# chessclock.net
KiCad netlist of a schematic drawn in EAGLE
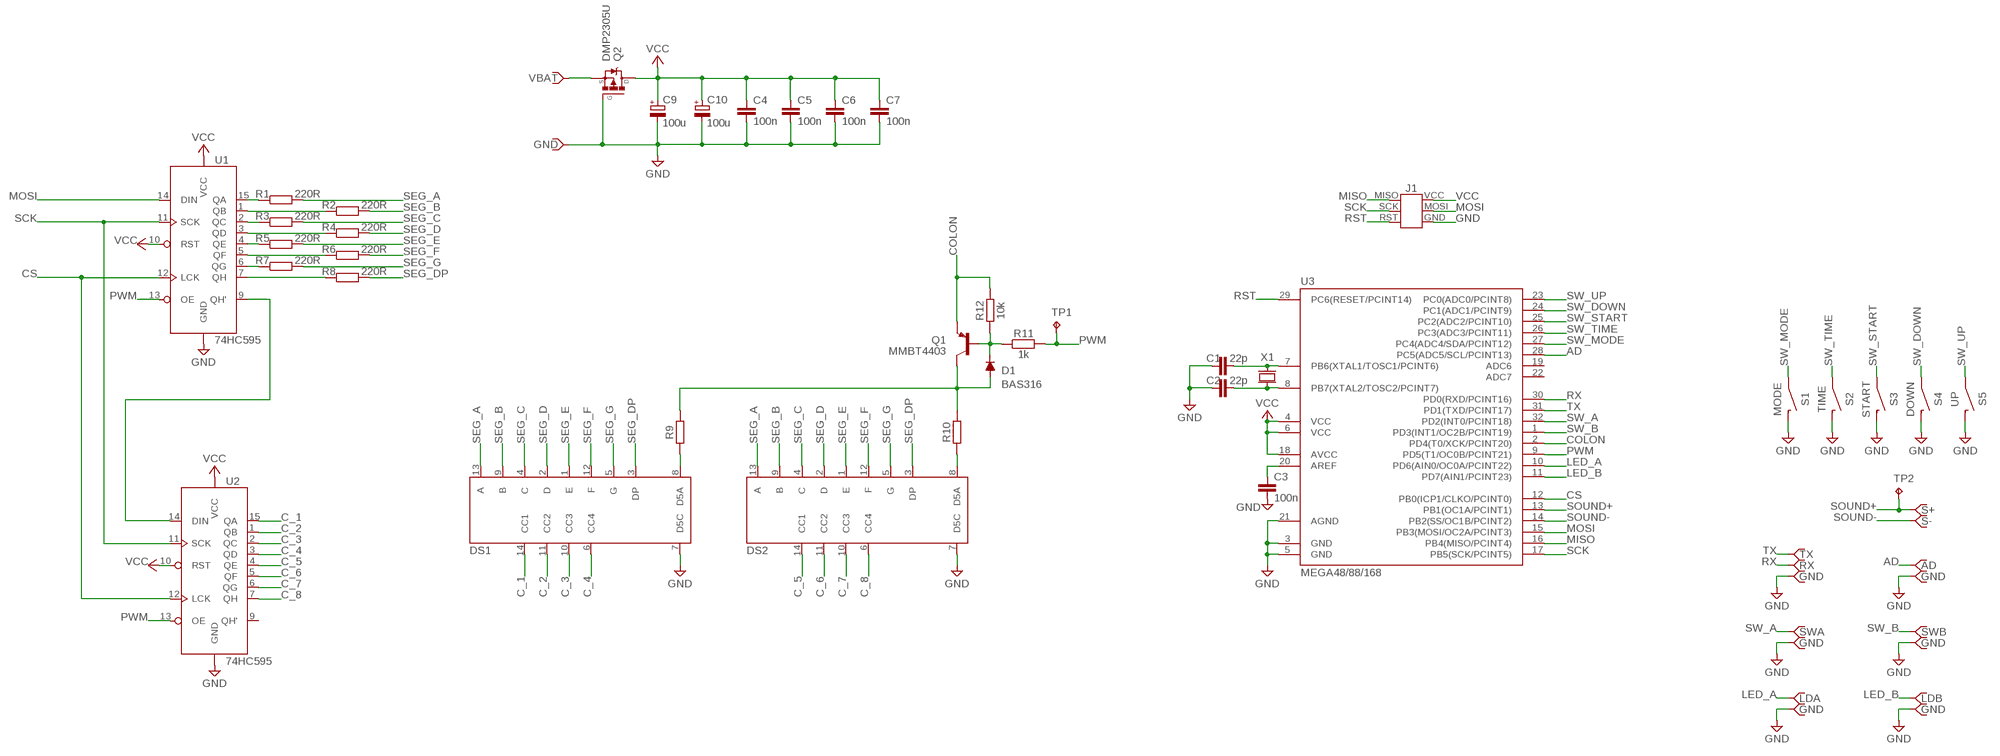
[diagram p0: schematic, sheet 1]

(export (version "E")
  (design (tool "Eeschema 10.0.6"))
  (components
    (comp (ref "C1")
      (value "22p")
      (footprint "eagle-import:C_0603")
      (libsource (lib "eagle-import") (part "CAPACITOR0603"))
    )
    (comp (ref "C2")
      (value "22p")
      (footprint "eagle-import:C_0603")
      (libsource (lib "eagle-import") (part "CAPACITOR0603"))
    )
    (comp (ref "C3")
      (value "100n")
      (footprint "eagle-import:C_0603")
      (libsource (lib "eagle-import") (part "CAPACITOR0603"))
    )
    (comp (ref "C4")
      (value "100n")
      (footprint "eagle-import:C_0603")
      (libsource (lib "eagle-import") (part "CAPACITOR0603"))
    )
    (comp (ref "C5")
      (value "100n")
      (footprint "eagle-import:C_0603")
      (libsource (lib "eagle-import") (part "CAPACITOR0603"))
    )
    (comp (ref "C6")
      (value "100n")
      (footprint "eagle-import:C_0603")
      (libsource (lib "eagle-import") (part "CAPACITOR0603"))
    )
    (comp (ref "C7")
      (value "100n")
      (footprint "eagle-import:C_0603")
      (libsource (lib "eagle-import") (part "CAPACITOR0603"))
    )
    (comp (ref "C9")
      (value "100u")
      (footprint "eagle-import:C_E_TH_FLAT_L_5MM")
      (libsource (lib "eagle-import") (part "CAPACITOR_POLARISEDTH_FLAT_L_5MM"))
    )
    (comp (ref "C10")
      (value "100u")
      (footprint "eagle-import:C_E_TH_FLAT_L_5MM")
      (libsource (lib "eagle-import") (part "CAPACITOR_POLARISEDTH_FLAT_L_5MM"))
    )
    (comp (ref "D1")
      (value "BAS316")
      (footprint "eagle-import:SOD323")
      (libsource (lib "eagle-import") (part "BAS316"))
    )
    (comp (ref "DS1")
      (value "SLR0564FR1C4BD-3.5")
      (footprint "eagle-import:SLR0564FR1C4BD-3.5")
      (libsource (lib "eagle-import") (part "SLR0564FR1C4BD-3.5"))
    )
    (comp (ref "DS2")
      (value "SLR0564FR1C4BD-3.5")
      (footprint "eagle-import:SLR0564FR1C4BD-3.5")
      (libsource (lib "eagle-import") (part "SLR0564FR1C4BD-3.5"))
    )
    (comp (ref "J1")
      (value "AVRISPVERT")
      (footprint "eagle-import:AVRISP")
      (libsource (lib "eagle-import") (part "AVRISPVERT"))
    )
    (comp (ref "P1")
      (value "SWA")
      (footprint "eagle-import:CON_PIN_2MM")
      (libsource (lib "eagle-import") (part "CON_PIN_2MM"))
    )
    (comp (ref "P2")
      (value "GND")
      (footprint "eagle-import:CON_PIN_2MM")
      (libsource (lib "eagle-import") (part "CON_PIN_2MM"))
    )
    (comp (ref "P3")
      (value "LDA")
      (footprint "eagle-import:CON_PIN_2MM")
      (libsource (lib "eagle-import") (part "CON_PIN_2MM"))
    )
    (comp (ref "P4")
      (value "GND")
      (footprint "eagle-import:CON_PIN_2MM")
      (libsource (lib "eagle-import") (part "CON_PIN_2MM"))
    )
    (comp (ref "P5")
      (value "SWB")
      (footprint "eagle-import:CON_PIN_2MM")
      (libsource (lib "eagle-import") (part "CON_PIN_2MM"))
    )
    (comp (ref "P6")
      (value "GND")
      (footprint "eagle-import:CON_PIN_2MM")
      (libsource (lib "eagle-import") (part "CON_PIN_2MM"))
    )
    (comp (ref "P7")
      (value "LDB")
      (footprint "eagle-import:CON_PIN_2MM")
      (libsource (lib "eagle-import") (part "CON_PIN_2MM"))
    )
    (comp (ref "P8")
      (value "GND")
      (footprint "eagle-import:CON_PIN_2MM")
      (libsource (lib "eagle-import") (part "CON_PIN_2MM"))
    )
    (comp (ref "P9")
      (value "GND")
      (footprint "eagle-import:CON_PIN_2MM")
      (libsource (lib "eagle-import") (part "CON_PIN_2MM"))
    )
    (comp (ref "P10")
      (value "VBAT")
      (footprint "eagle-import:CON_PIN_2MM")
      (libsource (lib "eagle-import") (part "CON_PIN_2MM"))
    )
    (comp (ref "P11")
      (value "S+")
      (footprint "eagle-import:CON_PIN_2MM")
      (libsource (lib "eagle-import") (part "CON_PIN_2MM"))
    )
    (comp (ref "P12")
      (value "S-")
      (footprint "eagle-import:CON_PIN_2MM")
      (libsource (lib "eagle-import") (part "CON_PIN_2MM"))
    )
    (comp (ref "P13")
      (value "GND")
      (footprint "eagle-import:CON_PIN")
      (libsource (lib "eagle-import") (part "CON_PIN"))
    )
    (comp (ref "P14")
      (value "RX")
      (footprint "eagle-import:CON_PIN")
      (libsource (lib "eagle-import") (part "CON_PIN"))
    )
    (comp (ref "P15")
      (value "TX")
      (footprint "eagle-import:CON_PIN")
      (libsource (lib "eagle-import") (part "CON_PIN"))
    )
    (comp (ref "P16")
      (value "GND")
      (footprint "eagle-import:CON_PIN")
      (libsource (lib "eagle-import") (part "CON_PIN"))
    )
    (comp (ref "P17")
      (value "AD")
      (footprint "eagle-import:CON_PIN")
      (libsource (lib "eagle-import") (part "CON_PIN"))
    )
    (comp (ref "Q1")
      (value "MMBT4403")
      (footprint "eagle-import:SOT23")
      (libsource (lib "eagle-import") (part "MMBT4403LT1"))
    )
    (comp (ref "Q2")
      (value "DMP2305U")
      (footprint "eagle-import:SOT23")
      (libsource (lib "eagle-import") (part "DMP2305U"))
    )
    (comp (ref "R1")
      (value "220R")
      (footprint "eagle-import:R_0603")
      (libsource (lib "eagle-import") (part "RESISTOR0603"))
    )
    (comp (ref "R2")
      (value "220R")
      (footprint "eagle-import:R_0603")
      (libsource (lib "eagle-import") (part "RESISTOR0603"))
    )
    (comp (ref "R3")
      (value "220R")
      (footprint "eagle-import:R_0603")
      (libsource (lib "eagle-import") (part "RESISTOR0603"))
    )
    (comp (ref "R4")
      (value "220R")
      (footprint "eagle-import:R_0603")
      (libsource (lib "eagle-import") (part "RESISTOR0603"))
    )
    (comp (ref "R5")
      (value "220R")
      (footprint "eagle-import:R_0603")
      (libsource (lib "eagle-import") (part "RESISTOR0603"))
    )
    (comp (ref "R6")
      (value "220R")
      (footprint "eagle-import:R_0603")
      (libsource (lib "eagle-import") (part "RESISTOR0603"))
    )
    (comp (ref "R7")
      (value "220R")
      (footprint "eagle-import:R_0603")
      (libsource (lib "eagle-import") (part "RESISTOR0603"))
    )
    (comp (ref "R8")
      (value "220R")
      (footprint "eagle-import:R_0603")
      (libsource (lib "eagle-import") (part "RESISTOR0603"))
    )
    (comp (ref "R9")
      (value "RESISTOR0603")
      (footprint "eagle-import:R_0603")
      (libsource (lib "eagle-import") (part "RESISTOR0603"))
    )
    (comp (ref "R10")
      (value "RESISTOR0603")
      (footprint "eagle-import:R_0603")
      (libsource (lib "eagle-import") (part "RESISTOR0603"))
    )
    (comp (ref "R11")
      (value "1k")
      (footprint "eagle-import:R_0603")
      (libsource (lib "eagle-import") (part "RESISTOR0603"))
    )
    (comp (ref "R12")
      (value "10k")
      (footprint "eagle-import:R_0603")
      (libsource (lib "eagle-import") (part "RESISTOR0603"))
    )
    (comp (ref "S1")
      (value "MODE")
      (footprint "eagle-import:SPST_6X6MM")
      (libsource (lib "eagle-import") (part "SPST_6X6MM"))
    )
    (comp (ref "S2")
      (value "TIME")
      (footprint "eagle-import:SPST_6X6MM")
      (libsource (lib "eagle-import") (part "SPST_6X6MM"))
    )
    (comp (ref "S3")
      (value "START")
      (footprint "eagle-import:SPST_6X6MM")
      (libsource (lib "eagle-import") (part "SPST_6X6MM"))
    )
    (comp (ref "S4")
      (value "DOWN")
      (footprint "eagle-import:SPST_6X6MM")
      (libsource (lib "eagle-import") (part "SPST_6X6MM"))
    )
    (comp (ref "S5")
      (value "UP")
      (footprint "eagle-import:SPST_6X6MM")
      (libsource (lib "eagle-import") (part "SPST_6X6MM"))
    )
    (comp (ref "TP1")
      (value "TPTP15R")
      (footprint "eagle-import:TP15R")
      (libsource (lib "eagle-import") (part "TPTP15R"))
    )
    (comp (ref "TP2")
      (value "TPTP15R")
      (footprint "eagle-import:TP15R")
      (libsource (lib "eagle-import") (part "TPTP15R"))
    )
    (comp (ref "U1")
      (value "74HC595")
      (footprint "eagle-import:SOIC16")
      (libsource (lib "eagle-import") (part "74HC595"))
    )
    (comp (ref "U2")
      (value "74HC595")
      (footprint "eagle-import:SOIC16")
      (libsource (lib "eagle-import") (part "74HC595"))
    )
    (comp (ref "U3")
      (value "MEGA48/88/168")
      (footprint "eagle-import:TQFP32-08")
      (libsource (lib "eagle-import") (part "MEGA48/88/168"))
    )
    (comp (ref "X1")
      (value "XTAL_32768HZ2X6")
      (footprint "eagle-import:XTAL_2X6MM")
      (libsource (lib "eagle-import") (part "XTAL_32768HZ2X6"))
    )
  )
  (nets
    (net (code "1") (name "/AD") (class "Default")
      (node (ref "P17") (pin "1") (pinfunction "1_1") (pintype "bidirectional"))
      (node (ref "U3") (pin "28") (pinfunction "PC5(ADC5/SCL/PCINT13)_28") (pintype "bidirectional"))
    )
    (net (code "2") (name "/COLON") (class "Default")
      (node (ref "Q1") (pin "2") (pinfunction "E_2") (pintype "passive"))
      (node (ref "R12") (pin "2") (pinfunction "2_2") (pintype "passive"))
      (node (ref "U3") (pin "2") (pinfunction "PD4(T0/XCK/PCINT20)_2") (pintype "bidirectional"))
    )
    (net (code "3") (name "/CS") (class "Default")
      (node (ref "U1") (pin "12") (pinfunction "LCK_12") (pintype "input"))
      (node (ref "U2") (pin "12") (pinfunction "LCK_12") (pintype "input"))
      (node (ref "U3") (pin "12") (pinfunction "PB0(ICP1/CLKO/PCINT0)_12") (pintype "bidirectional"))
    )
    (net (code "4") (name "/C_1") (class "Default")
      (node (ref "DS1") (pin "14") (pinfunction "CC1_14") (pintype "bidirectional"))
      (node (ref "U2") (pin "15") (pinfunction "QA_15") (pintype "tri_state"))
    )
    (net (code "5") (name "/C_2") (class "Default")
      (node (ref "DS1") (pin "11") (pinfunction "CC2_11") (pintype "bidirectional"))
      (node (ref "U2") (pin "1") (pinfunction "QB_1") (pintype "tri_state"))
    )
    (net (code "6") (name "/C_3") (class "Default")
      (node (ref "DS1") (pin "10") (pinfunction "CC3_10") (pintype "bidirectional"))
      (node (ref "U2") (pin "2") (pinfunction "QC_2") (pintype "tri_state"))
    )
    (net (code "7") (name "/C_4") (class "Default")
      (node (ref "DS1") (pin "6") (pinfunction "CC4_6") (pintype "bidirectional"))
      (node (ref "U2") (pin "3") (pinfunction "QD_3") (pintype "tri_state"))
    )
    (net (code "8") (name "/C_5") (class "Default")
      (node (ref "DS2") (pin "14") (pinfunction "CC1_14") (pintype "bidirectional"))
      (node (ref "U2") (pin "4") (pinfunction "QE_4") (pintype "tri_state"))
    )
    (net (code "9") (name "/C_6") (class "Default")
      (node (ref "DS2") (pin "11") (pinfunction "CC2_11") (pintype "bidirectional"))
      (node (ref "U2") (pin "5") (pinfunction "QF_5") (pintype "tri_state"))
    )
    (net (code "10") (name "/C_7") (class "Default")
      (node (ref "DS2") (pin "10") (pinfunction "CC3_10") (pintype "bidirectional"))
      (node (ref "U2") (pin "6") (pinfunction "QG_6") (pintype "tri_state"))
    )
    (net (code "11") (name "/C_8") (class "Default")
      (node (ref "DS2") (pin "6") (pinfunction "CC4_6") (pintype "bidirectional"))
      (node (ref "U2") (pin "7") (pinfunction "QH_7") (pintype "tri_state"))
    )
    (net (code "12") (name "/LED_A") (class "Default")
      (node (ref "P3") (pin "1") (pinfunction "1_1") (pintype "bidirectional"))
      (node (ref "U3") (pin "10") (pinfunction "PD6(AIN0/OC0A/PCINT22)_10") (pintype "bidirectional"))
    )
    (net (code "13") (name "/LED_B") (class "Default")
      (node (ref "P7") (pin "1") (pinfunction "1_1") (pintype "bidirectional"))
      (node (ref "U3") (pin "11") (pinfunction "PD7(AIN1/PCINT23)_11") (pintype "bidirectional"))
    )
    (net (code "14") (name "/MISO") (class "Default")
      (node (ref "J1") (pin "MISO") (pinfunction "1_MISO") (pintype "passive"))
      (node (ref "U3") (pin "16") (pinfunction "PB4(MISO/PCINT4)_16") (pintype "bidirectional"))
    )
    (net (code "15") (name "/MOSI") (class "Default")
      (node (ref "J1") (pin "MOSI") (pinfunction "4_MOSI") (pintype "passive"))
      (node (ref "U1") (pin "14") (pinfunction "DIN_14") (pintype "input"))
      (node (ref "U3") (pin "15") (pinfunction "PB3(MOSI/OC2A/PCINT3)_15") (pintype "bidirectional"))
    )
    (net (code "16") (name "/PWM") (class "Default")
      (node (ref "R11") (pin "2") (pinfunction "2_2") (pintype "passive"))
      (node (ref "TP1") (pin "TP") (pinfunction "TP_TP") (pintype "input"))
      (node (ref "U1") (pin "13") (pinfunction "OE_13") (pintype "input"))
      (node (ref "U2") (pin "13") (pinfunction "OE_13") (pintype "input"))
      (node (ref "U3") (pin "9") (pinfunction "PD5(T1/OC0B/PCINT21)_9") (pintype "bidirectional"))
    )
    (net (code "17") (name "/RST") (class "Default")
      (node (ref "J1") (pin "RST") (pinfunction "5_RST") (pintype "passive"))
      (node (ref "U3") (pin "29") (pinfunction "PC6(RESET/PCINT14)_29") (pintype "bidirectional"))
    )
    (net (code "18") (name "/RX") (class "Default")
      (node (ref "P14") (pin "1") (pinfunction "1_1") (pintype "bidirectional"))
      (node (ref "U3") (pin "30") (pinfunction "PD0(RXD/PCINT16)_30") (pintype "bidirectional"))
    )
    (net (code "19") (name "/SCK") (class "Default")
      (node (ref "J1") (pin "SCK") (pinfunction "3_SCK") (pintype "passive"))
      (node (ref "U1") (pin "11") (pinfunction "SCK_11") (pintype "input"))
      (node (ref "U2") (pin "11") (pinfunction "SCK_11") (pintype "input"))
      (node (ref "U3") (pin "17") (pinfunction "PB5(SCK/PCINT5)_17") (pintype "bidirectional"))
    )
    (net (code "20") (name "/SEG_A") (class "Default")
      (node (ref "DS1") (pin "13") (pinfunction "A_13") (pintype "bidirectional"))
      (node (ref "DS2") (pin "13") (pinfunction "A_13") (pintype "bidirectional"))
      (node (ref "R1") (pin "2") (pinfunction "2_2") (pintype "passive"))
    )
    (net (code "21") (name "/SEG_B") (class "Default")
      (node (ref "DS1") (pin "9") (pinfunction "B_9") (pintype "bidirectional"))
      (node (ref "DS2") (pin "9") (pinfunction "B_9") (pintype "bidirectional"))
      (node (ref "R2") (pin "2") (pinfunction "2_2") (pintype "passive"))
    )
    (net (code "22") (name "/SEG_C") (class "Default")
      (node (ref "DS1") (pin "4") (pinfunction "C_4") (pintype "bidirectional"))
      (node (ref "DS2") (pin "4") (pinfunction "C_4") (pintype "bidirectional"))
      (node (ref "R3") (pin "2") (pinfunction "2_2") (pintype "passive"))
    )
    (net (code "23") (name "/SEG_D") (class "Default")
      (node (ref "DS1") (pin "2") (pinfunction "D_2") (pintype "bidirectional"))
      (node (ref "DS2") (pin "2") (pinfunction "D_2") (pintype "bidirectional"))
      (node (ref "R4") (pin "2") (pinfunction "2_2") (pintype "passive"))
    )
    (net (code "24") (name "/SEG_DP") (class "Default")
      (node (ref "DS1") (pin "3") (pinfunction "DP_3") (pintype "bidirectional"))
      (node (ref "DS2") (pin "3") (pinfunction "DP_3") (pintype "bidirectional"))
      (node (ref "R8") (pin "2") (pinfunction "2_2") (pintype "passive"))
    )
    (net (code "25") (name "/SEG_E") (class "Default")
      (node (ref "DS1") (pin "1") (pinfunction "E_1") (pintype "bidirectional"))
      (node (ref "DS2") (pin "1") (pinfunction "E_1") (pintype "bidirectional"))
      (node (ref "R5") (pin "2") (pinfunction "2_2") (pintype "passive"))
    )
    (net (code "26") (name "/SEG_F") (class "Default")
      (node (ref "DS1") (pin "12") (pinfunction "F_12") (pintype "bidirectional"))
      (node (ref "DS2") (pin "12") (pinfunction "F_12") (pintype "bidirectional"))
      (node (ref "R6") (pin "2") (pinfunction "2_2") (pintype "passive"))
    )
    (net (code "27") (name "/SEG_G") (class "Default")
      (node (ref "DS1") (pin "5") (pinfunction "G_5") (pintype "bidirectional"))
      (node (ref "DS2") (pin "5") (pinfunction "G_5") (pintype "bidirectional"))
      (node (ref "R7") (pin "2") (pinfunction "2_2") (pintype "passive"))
    )
    (net (code "28") (name "/SOUND+") (class "Default")
      (node (ref "P11") (pin "1") (pinfunction "1_1") (pintype "bidirectional"))
      (node (ref "TP2") (pin "TP") (pinfunction "TP_TP") (pintype "input"))
      (node (ref "U3") (pin "13") (pinfunction "PB1(OC1A/PCINT1)_13") (pintype "bidirectional"))
    )
    (net (code "29") (name "/SOUND-") (class "Default")
      (node (ref "P12") (pin "1") (pinfunction "1_1") (pintype "bidirectional"))
      (node (ref "U3") (pin "14") (pinfunction "PB2(SS/OC1B/PCINT2)_14") (pintype "bidirectional"))
    )
    (net (code "30") (name "/SW_A") (class "Default")
      (node (ref "P1") (pin "1") (pinfunction "1_1") (pintype "bidirectional"))
      (node (ref "U3") (pin "32") (pinfunction "PD2(INT0/PCINT18)_32") (pintype "bidirectional"))
    )
    (net (code "31") (name "/SW_B") (class "Default")
      (node (ref "P5") (pin "1") (pinfunction "1_1") (pintype "bidirectional"))
      (node (ref "U3") (pin "1") (pinfunction "PD3(INT1/OC2B/PCINT19)_1") (pintype "bidirectional"))
    )
    (net (code "32") (name "/SW_DOWN") (class "Default")
      (node (ref "S4") (pin "1") (pinfunction "1_1") (pintype "passive"))
      (node (ref "S4") (pin "2") (pinfunction "1_2") (pintype "passive"))
      (node (ref "U3") (pin "24") (pinfunction "PC1(ADC1/PCINT9)_24") (pintype "bidirectional"))
    )
    (net (code "33") (name "/SW_MODE") (class "Default")
      (node (ref "S1") (pin "1") (pinfunction "1_1") (pintype "passive"))
      (node (ref "S1") (pin "2") (pinfunction "1_2") (pintype "passive"))
      (node (ref "U3") (pin "27") (pinfunction "PC4(ADC4/SDA/PCINT12)_27") (pintype "bidirectional"))
    )
    (net (code "34") (name "/SW_START") (class "Default")
      (node (ref "S3") (pin "1") (pinfunction "1_1") (pintype "passive"))
      (node (ref "S3") (pin "2") (pinfunction "1_2") (pintype "passive"))
      (node (ref "U3") (pin "25") (pinfunction "PC2(ADC2/PCINT10)_25") (pintype "bidirectional"))
    )
    (net (code "35") (name "/SW_TIME") (class "Default")
      (node (ref "S2") (pin "1") (pinfunction "1_1") (pintype "passive"))
      (node (ref "S2") (pin "2") (pinfunction "1_2") (pintype "passive"))
      (node (ref "U3") (pin "26") (pinfunction "PC3(ADC3/PCINT11)_26") (pintype "bidirectional"))
    )
    (net (code "36") (name "/SW_UP") (class "Default")
      (node (ref "S5") (pin "1") (pinfunction "1_1") (pintype "passive"))
      (node (ref "S5") (pin "2") (pinfunction "1_2") (pintype "passive"))
      (node (ref "U3") (pin "23") (pinfunction "PC0(ADC0/PCINT8)_23") (pintype "bidirectional"))
    )
    (net (code "37") (name "/TX") (class "Default")
      (node (ref "P15") (pin "1") (pinfunction "1_1") (pintype "bidirectional"))
      (node (ref "U3") (pin "31") (pinfunction "PD1(TXD/PCINT17)_31") (pintype "bidirectional"))
    )
    (net (code "38") (name "GND") (class "Default")
      (node (ref "C1") (pin "2") (pinfunction "2_2") (pintype "passive"))
      (node (ref "C10") (pin "-") (pinfunction "-_-") (pintype "passive"))
      (node (ref "C2") (pin "2") (pinfunction "2_2") (pintype "passive"))
      (node (ref "C3") (pin "1") (pinfunction "1_1") (pintype "passive"))
      (node (ref "C4") (pin "1") (pinfunction "1_1") (pintype "passive"))
      (node (ref "C5") (pin "1") (pinfunction "1_1") (pintype "passive"))
      (node (ref "C6") (pin "1") (pinfunction "1_1") (pintype "passive"))
      (node (ref "C7") (pin "1") (pinfunction "1_1") (pintype "passive"))
      (node (ref "C9") (pin "-") (pinfunction "-_-") (pintype "passive"))
      (node (ref "DS1") (pin "7") (pinfunction "D5C_7") (pintype "bidirectional"))
      (node (ref "DS2") (pin "7") (pinfunction "D5C_7") (pintype "bidirectional"))
      (node (ref "J1") (pin "GND") (pinfunction "6_GND") (pintype "passive"))
      (node (ref "P13") (pin "1") (pinfunction "1_1") (pintype "bidirectional"))
      (node (ref "P16") (pin "1") (pinfunction "1_1") (pintype "bidirectional"))
      (node (ref "P2") (pin "1") (pinfunction "1_1") (pintype "bidirectional"))
      (node (ref "P4") (pin "1") (pinfunction "1_1") (pintype "bidirectional"))
      (node (ref "P6") (pin "1") (pinfunction "1_1") (pintype "bidirectional"))
      (node (ref "P8") (pin "1") (pinfunction "1_1") (pintype "bidirectional"))
      (node (ref "P9") (pin "1") (pinfunction "1_1") (pintype "bidirectional"))
      (node (ref "Q2") (pin "1") (pinfunction "G_1") (pintype "passive"))
      (node (ref "S1") (pin "3") (pinfunction "2_3") (pintype "passive"))
      (node (ref "S1") (pin "4") (pinfunction "2_4") (pintype "passive"))
      (node (ref "S2") (pin "3") (pinfunction "2_3") (pintype "passive"))
      (node (ref "S2") (pin "4") (pinfunction "2_4") (pintype "passive"))
      (node (ref "S3") (pin "3") (pinfunction "2_3") (pintype "passive"))
      (node (ref "S3") (pin "4") (pinfunction "2_4") (pintype "passive"))
      (node (ref "S4") (pin "3") (pinfunction "2_3") (pintype "passive"))
      (node (ref "S4") (pin "4") (pinfunction "2_4") (pintype "passive"))
      (node (ref "S5") (pin "3") (pinfunction "2_3") (pintype "passive"))
      (node (ref "S5") (pin "4") (pinfunction "2_4") (pintype "passive"))
      (node (ref "U1") (pin "8") (pinfunction "GND_8") (pintype "power_in"))
      (node (ref "U2") (pin "8") (pinfunction "GND_8") (pintype "power_in"))
      (node (ref "U3") (pin "21") (pinfunction "AGND_21") (pintype "power_in"))
      (node (ref "U3") (pin "3") (pinfunction "GND_3") (pintype "power_in"))
      (node (ref "U3") (pin "5") (pinfunction "GND_5") (pintype "power_in"))
    )
    (net (code "39") (name "Net-(DS1-D5A)") (class "Default")
      (node (ref "DS1") (pin "8") (pinfunction "D5A_8") (pintype "bidirectional"))
      (node (ref "R9") (pin "1") (pinfunction "1_1") (pintype "passive"))
    )
    (net (code "40") (name "Net-(DS2-D5A)") (class "Default")
      (node (ref "DS2") (pin "8") (pinfunction "D5A_8") (pintype "bidirectional"))
      (node (ref "R10") (pin "1") (pinfunction "1_1") (pintype "passive"))
    )
    (net (code "41") (name "Net-(Q1-B)") (class "Default")
      (node (ref "D1") (pin "C") (pinfunction "C_C") (pintype "passive"))
      (node (ref "Q1") (pin "1") (pinfunction "B_1") (pintype "passive"))
      (node (ref "R11") (pin "1") (pinfunction "1_1") (pintype "passive"))
      (node (ref "R12") (pin "1") (pinfunction "1_1") (pintype "passive"))
    )
    (net (code "42") (name "Net-(Q1-C)") (class "Default")
      (node (ref "D1") (pin "A") (pinfunction "A_A") (pintype "passive"))
      (node (ref "Q1") (pin "3") (pinfunction "C_3") (pintype "passive"))
      (node (ref "R10") (pin "2") (pinfunction "2_2") (pintype "passive"))
      (node (ref "R9") (pin "2") (pinfunction "2_2") (pintype "passive"))
    )
    (net (code "43") (name "Net-(Q2-S)") (class "Default")
      (node (ref "P10") (pin "1") (pinfunction "1_1") (pintype "bidirectional"))
      (node (ref "Q2") (pin "2") (pinfunction "S_2") (pintype "passive"))
    )
    (net (code "44") (name "Net-(U1-QA)") (class "Default")
      (node (ref "R1") (pin "1") (pinfunction "1_1") (pintype "passive"))
      (node (ref "U1") (pin "15") (pinfunction "QA_15") (pintype "tri_state"))
    )
    (net (code "45") (name "Net-(U1-QB)") (class "Default")
      (node (ref "R2") (pin "1") (pinfunction "1_1") (pintype "passive"))
      (node (ref "U1") (pin "1") (pinfunction "QB_1") (pintype "tri_state"))
    )
    (net (code "46") (name "Net-(U1-QC)") (class "Default")
      (node (ref "R3") (pin "1") (pinfunction "1_1") (pintype "passive"))
      (node (ref "U1") (pin "2") (pinfunction "QC_2") (pintype "tri_state"))
    )
    (net (code "47") (name "Net-(U1-QD)") (class "Default")
      (node (ref "R4") (pin "1") (pinfunction "1_1") (pintype "passive"))
      (node (ref "U1") (pin "3") (pinfunction "QD_3") (pintype "tri_state"))
    )
    (net (code "48") (name "Net-(U1-QE)") (class "Default")
      (node (ref "R5") (pin "1") (pinfunction "1_1") (pintype "passive"))
      (node (ref "U1") (pin "4") (pinfunction "QE_4") (pintype "tri_state"))
    )
    (net (code "49") (name "Net-(U1-QF)") (class "Default")
      (node (ref "R6") (pin "1") (pinfunction "1_1") (pintype "passive"))
      (node (ref "U1") (pin "5") (pinfunction "QF_5") (pintype "tri_state"))
    )
    (net (code "50") (name "Net-(U1-QG)") (class "Default")
      (node (ref "R7") (pin "1") (pinfunction "1_1") (pintype "passive"))
      (node (ref "U1") (pin "6") (pinfunction "QG_6") (pintype "tri_state"))
    )
    (net (code "51") (name "Net-(U1-QH')") (class "Default")
      (node (ref "U1") (pin "9") (pinfunction "QH'_9") (pintype "tri_state"))
      (node (ref "U2") (pin "14") (pinfunction "DIN_14") (pintype "input"))
    )
    (net (code "52") (name "Net-(U1-QH)") (class "Default")
      (node (ref "R8") (pin "1") (pinfunction "1_1") (pintype "passive"))
      (node (ref "U1") (pin "7") (pinfunction "QH_7") (pintype "tri_state"))
    )
    (net (code "53") (name "Net-(U3-AREF)") (class "Default")
      (node (ref "C3") (pin "2") (pinfunction "2_2") (pintype "passive"))
      (node (ref "U3") (pin "20") (pinfunction "AREF_20") (pintype "passive"))
    )
    (net (code "54") (name "Net-(U3-PB6(XTAL1{slash}TOSC1{slash}PCINT6))") (class "Default")
      (node (ref "C1") (pin "1") (pinfunction "1_1") (pintype "passive"))
      (node (ref "U3") (pin "7") (pinfunction "PB6(XTAL1/TOSC1/PCINT6)_7") (pintype "bidirectional"))
      (node (ref "X1") (pin "1") (pinfunction "1_1") (pintype "passive"))
    )
    (net (code "55") (name "Net-(U3-PB7(XTAL2{slash}TOSC2{slash}PCINT7))") (class "Default")
      (node (ref "C2") (pin "1") (pinfunction "1_1") (pintype "passive"))
      (node (ref "U3") (pin "8") (pinfunction "PB7(XTAL2/TOSC2/PCINT7)_8") (pintype "bidirectional"))
      (node (ref "X1") (pin "2") (pinfunction "2_2") (pintype "passive"))
    )
    (net (code "56") (name "VCC") (class "Default")
      (node (ref "C10") (pin "+") (pinfunction "+_+") (pintype "passive"))
      (node (ref "C4") (pin "2") (pinfunction "2_2") (pintype "passive"))
      (node (ref "C5") (pin "2") (pinfunction "2_2") (pintype "passive"))
      (node (ref "C6") (pin "2") (pinfunction "2_2") (pintype "passive"))
      (node (ref "C7") (pin "2") (pinfunction "2_2") (pintype "passive"))
      (node (ref "C9") (pin "+") (pinfunction "+_+") (pintype "passive"))
      (node (ref "J1") (pin "VCC") (pinfunction "2_VCC") (pintype "passive"))
      (node (ref "Q2") (pin "3") (pinfunction "D_3") (pintype "passive"))
      (node (ref "U1") (pin "10") (pinfunction "RST_10") (pintype "input"))
      (node (ref "U1") (pin "16") (pinfunction "VCC_16") (pintype "power_in"))
      (node (ref "U2") (pin "10") (pinfunction "RST_10") (pintype "input"))
      (node (ref "U2") (pin "16") (pinfunction "VCC_16") (pintype "power_in"))
      (node (ref "U3") (pin "18") (pinfunction "AVCC_18") (pintype "passive"))
      (node (ref "U3") (pin "4") (pinfunction "VCC_4") (pintype "power_in"))
      (node (ref "U3") (pin "6") (pinfunction "VCC_6") (pintype "power_in"))
    )
    (net (code "57") (name "unconnected-(U2-QH'-Pad9)") (class "Default")
      (node (ref "U2") (pin "9") (pinfunction "QH'_9") (pintype "tri_state"))
    )
    (net (code "58") (name "unconnected-(U3-ADC6-Pad19)") (class "Default")
      (node (ref "U3") (pin "19") (pinfunction "ADC6_19") (pintype "passive"))
    )
    (net (code "59") (name "unconnected-(U3-ADC7-Pad22)") (class "Default")
      (node (ref "U3") (pin "22") (pinfunction "ADC7_22") (pintype "passive"))
    )
  )
)
